# MCMainSch.net
KiCad netlist of a schematic drawn in Altium Designer
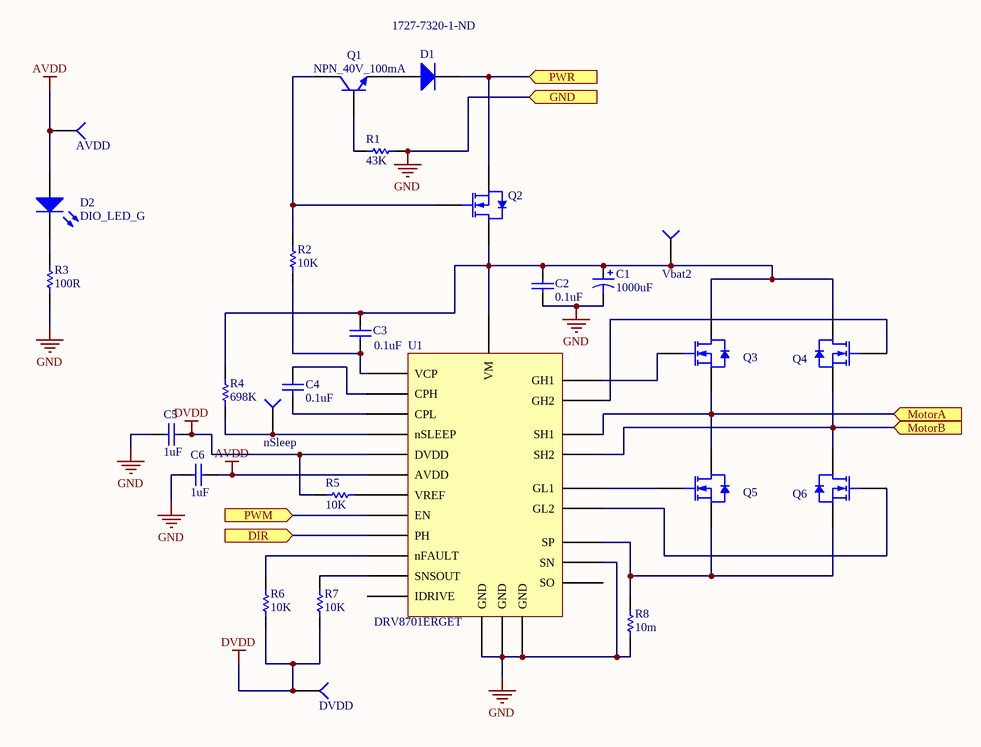
[diagram p0: MCMainSch.SchDoc]

(export (version "E")
  (design (tool "Eeschema 10.0.6"))
  (components
    (comp (ref "C1")
      (value "1000uF")
      (footprint "CAPR-2/4h6.8")
      (description "CAP ALUM 22UF 20% 50V RADIAL")
      (fields (field (name "MANUFACTURER") "Wurth Electronics Inc.") (field (name "MPN") "860020672011"))
      (libsource (lib "UWRT_Schematic_Library_2019") (part "CAP_22uF_POL"))
    )
    (comp (ref "C2")
      (value "0.1uF")
      (footprint "CAPC0603(1608)55_N")
      (description "CAP CER 0.1UF 16V X7R 0603")
      (fields (field (name "MPN") "CC0603KRX7R7BB104") (field (name "MANUFACTURER") "Yageo"))
      (libsource (lib "UWRT_Schematic_Library_2019") (part "CAP_0.1uF_16V_0603"))
    )
    (comp (ref "C3")
      (value "0.1uF")
      (footprint "CAPC0603(1608)55_N")
      (description "CAP CER 0.1UF 16V X7R 0603")
      (fields (field (name "MPN") "CC0603KRX7R7BB104") (field (name "MANUFACTURER") "Yageo"))
      (libsource (lib "UWRT_Schematic_Library_2019") (part "CAP_0.1uF_16V_0603"))
    )
    (comp (ref "C4")
      (value "0.1uF")
      (footprint "CAPC0603(1608)55_N")
      (description "CAP CER 0.1UF 16V X7R 0603")
      (fields (field (name "MPN") "CC0603KRX7R7BB104") (field (name "MANUFACTURER") "Yageo"))
      (libsource (lib "UWRT_Schematic_Library_2019") (part "CAP_0.1uF_16V_0603"))
    )
    (comp (ref "C5")
      (value "1uF")
      (footprint "CAPC0603(1608)55_N")
      (description "CAP CER 1UF 16V Y5V 0603")
      (fields (field (name "MPN") "CC0603ZRY5V7BB105") (field (name "MANUFACTURER") "Yageo"))
      (libsource (lib "UWRT_Schematic_Library_2019") (part "CAP_1uF_16V_0603"))
    )
    (comp (ref "C6")
      (value "1uF")
      (footprint "CAPC0603(1608)55_N")
      (description "CAP CER 1UF 16V Y5V 0603")
      (fields (field (name "MPN") "CC0603ZRY5V7BB105") (field (name "MANUFACTURER") "Yageo"))
      (libsource (lib "UWRT_Schematic_Library_2019") (part "CAP_1uF_16V_0603"))
    )
    (comp (ref "D1")
      (value "0")
      (footprint "DIODSOD-123")
      (description "ESD PROTECTION DIODE")
      (fields
        (field (name "MPN") "BAS16GW")
        (field (name "MANUFACTURER") "Nexperia")
        (field (name "SUPPLIER PART NUMBER 1") "1727-7320-1-ND")
      )
      (libsource (lib "UWRT_Schematic_Library_2019") (part "DIO_BAS16GW"))
    )
    (comp (ref "D2")
      (value "DIO_LED_G")
      (footprint "LED_0805_LINE")
      (description "LED GREEN DIFFUSED 0805 SMD")
      (fields (field (name "MPN") "LG R971-KN-1") (field (name "MANUFACTURER") "OSRAM"))
      (libsource (lib "UWRT_Schematic_Library_2019") (part "DIO_LED_G"))
    )
    (comp (ref "Q1")
      (value "NPN_40V_100mA")
      (footprint "SOT23-3")
      (description "TRANS NPN 40V 0.2A SOT23")
      (fields (field (name "MANUFACTURER") "Micro Commercial Co") (field (name "MPN") "MMBT3904-TP"))
      (libsource (lib "UWRT_Schematic_Library_2019") (part "NPN_40V_100mA"))
    )
    (comp (ref "Q2")
      (value "NMOS_40V_75A")
      (footprint "SOT404")
      (description "MOSFET N-CH 40V 75A D2PAK")
      (fields (field (name "MPN") "BUK768R1-40E,118") (field (name "MANUFACTURER") "Nexperia USA Inc."))
      (libsource (lib "UWRT_Schematic_Library_2019") (part "NMOS_40V_75A"))
    )
    (comp (ref "Q3")
      (value "NMOS_40V_75A")
      (footprint "SOT404")
      (description "MOSFET N-CH 40V 75A D2PAK")
      (fields (field (name "MPN") "BUK768R1-40E,118") (field (name "MANUFACTURER") "Nexperia USA Inc."))
      (libsource (lib "UWRT_Schematic_Library_2019") (part "NMOS_40V_75A"))
    )
    (comp (ref "Q4")
      (value "NMOS_40V_75A")
      (footprint "SOT404")
      (description "MOSFET N-CH 40V 75A D2PAK")
      (fields (field (name "MPN") "BUK768R1-40E,118") (field (name "MANUFACTURER") "Nexperia USA Inc."))
      (libsource (lib "UWRT_Schematic_Library_2019") (part "NMOS_40V_75A"))
    )
    (comp (ref "Q5")
      (value "NMOS_40V_75A")
      (footprint "SOT404")
      (description "MOSFET N-CH 40V 75A D2PAK")
      (fields (field (name "MPN") "BUK768R1-40E,118") (field (name "MANUFACTURER") "Nexperia USA Inc."))
      (libsource (lib "UWRT_Schematic_Library_2019") (part "NMOS_40V_75A"))
    )
    (comp (ref "Q6")
      (value "NMOS_40V_75A")
      (footprint "SOT404")
      (description "MOSFET N-CH 40V 75A D2PAK")
      (fields (field (name "MPN") "BUK768R1-40E,118") (field (name "MANUFACTURER") "Nexperia USA Inc."))
      (libsource (lib "UWRT_Schematic_Library_2019") (part "NMOS_40V_75A"))
    )
    (comp (ref "R1")
      (value "43K")
      (footprint "RESC0603(1608)_N")
      (description "RES SMD 43K OHM 5% 1/10W 0603")
      (fields (field (name "MANUFACTURER") "Yageo") (field (name "MPN") "RC0603JR-0743KL"))
      (libsource (lib "UWRT_Schematic_Library_2019") (part "RES_43K_0603"))
    )
    (comp (ref "R2")
      (value "10K")
      (footprint "RESC0603(1608)_N")
      (description "RES SMD 10K OHM 5% 1/10W 0603")
      (fields (field (name "MANUFACTURER") "Yageo") (field (name "MPN") "RC0603JR-0710KL"))
      (libsource (lib "UWRT_Schematic_Library_2019") (part "RES_10K_0603"))
    )
    (comp (ref "R3")
      (value "100R")
      (footprint "RESC0603(1608)_N")
      (description "RES SMD 0 OHM JUMPER 1/10W 0603")
      (fields (field (name "MANUFACTURER") "Yageo") (field (name "MPN") "RC0603JR-070RL"))
      (libsource (lib "UWRT_Schematic_Library_2019") (part "RES_0R_0603"))
    )
    (comp (ref "R4")
      (value "698K")
      (footprint "RESC0603(1608)_N")
      (description "RES SMD 698K OHM 1% 1/10W 0603")
      (fields (field (name "MANUFACTURER") "Yageo") (field (name "MPN") "RC0603FR-07698KL"))
      (libsource (lib "UWRT_Schematic_Library_2019") (part "RES_698K_0603"))
    )
    (comp (ref "R5")
      (value "10K")
      (footprint "RESC0603(1608)_N")
      (description "RES SMD 10K OHM 5% 1/10W 0603")
      (fields (field (name "MANUFACTURER") "Yageo") (field (name "MPN") "RC0603JR-0710KL"))
      (libsource (lib "UWRT_Schematic_Library_2019") (part "RES_10K_0603"))
    )
    (comp (ref "R6")
      (value "10K")
      (footprint "RESC0603(1608)_N")
      (description "RES SMD 10K OHM 5% 1/10W 0603")
      (fields (field (name "MANUFACTURER") "Yageo") (field (name "MPN") "RC0603JR-0710KL"))
      (libsource (lib "UWRT_Schematic_Library_2019") (part "RES_10K_0603"))
    )
    (comp (ref "R7")
      (value "10K")
      (footprint "RESC0603(1608)_N")
      (description "RES SMD 10K OHM 5% 1/10W 0603")
      (fields (field (name "MANUFACTURER") "Yageo") (field (name "MPN") "RC0603JR-0710KL"))
      (libsource (lib "UWRT_Schematic_Library_2019") (part "RES_10K_0603"))
    )
    (comp (ref "R8")
      (value "10m")
      (footprint "STAC-CSS2725-099H_V")
      (description "RES SMD 10mOHM 1% 4W 2728")
      (fields (field (name "MANUFACTURER") "Yageo") (field (name "MPN") "RC0603FR-07698KL"))
      (libsource (lib "UWRT_Schematic_Library_2019") (part "RES_10m_2728"))
    )
    (comp (ref "TP1")
      (value "AVDD")
      (footprint "TESTPOINT")
      (description "TESTPOINT_SMD")
      (libsource (lib "UWRT_Schematic_Library_2019") (part "*"))
    )
    (comp (ref "TP2")
      (value "Vbat2")
      (footprint "TESTPOINT")
      (description "TESTPOINT_SMD")
      (libsource (lib "UWRT_Schematic_Library_2019") (part "*"))
    )
    (comp (ref "TP3")
      (value "nSleep")
      (footprint "TESTPOINT")
      (description "TESTPOINT_SMD")
      (libsource (lib "UWRT_Schematic_Library_2019") (part "*"))
    )
    (comp (ref "TP4")
      (value "DVDD")
      (footprint "TESTPOINT")
      (description "TESTPOINT_SMD")
      (libsource (lib "UWRT_Schematic_Library_2019") (part "*"))
    )
    (comp (ref "U1")
      (value "DRV8701ERGET")
      (footprint "VFQFPN-24_N")
      (fields (field (name "MANUFACTURER") "Texas Instruments"))
      (libsource (lib "UWRT_Schematic_Library_2019") (part "IC Motor Driver"))
    )
  )
  (nets
    (net (code "1") (name "/DIR") (class "Default")
      (node (ref "U1") (pin "15") (pinfunction "PH_15") (pintype "passive"))
    )
    (net (code "2") (name "/MotorA") (class "Default")
      (node (ref "Q3") (pin "3") (pinfunction "S_3") (pintype "passive"))
      (node (ref "Q5") (pin "4") (pinfunction "D_4") (pintype "passive"))
      (node (ref "U1") (pin "18") (pinfunction "SH1_18") (pintype "passive"))
    )
    (net (code "3") (name "/MotorB") (class "Default")
      (node (ref "Q4") (pin "3") (pinfunction "S_3") (pintype "passive"))
      (node (ref "Q6") (pin "4") (pinfunction "D_4") (pintype "passive"))
      (node (ref "U1") (pin "23") (pinfunction "SH2_23") (pintype "passive"))
    )
    (net (code "4") (name "/PWM") (class "Default")
      (node (ref "U1") (pin "14") (pinfunction "EN_14") (pintype "passive"))
    )
    (net (code "5") (name "/PWR") (class "Default")
      (node (ref "D1") (pin "2") (pinfunction "K_2") (pintype "passive"))
      (node (ref "Q2") (pin "3") (pinfunction "S_3") (pintype "passive"))
    )
    (net (code "6") (name "AVDD") (class "Default")
      (node (ref "C6") (pin "2") (pinfunction "2_2") (pintype "passive"))
      (node (ref "D2") (pin "1") (pinfunction "A_1") (pintype "passive"))
      (node (ref "TP1") (pin "1") (pinfunction "=value_1") (pintype "passive"))
      (node (ref "U1") (pin "7") (pinfunction "AVDD_7") (pintype "passive"))
    )
    (net (code "7") (name "DVDD") (class "Default")
      (node (ref "C5") (pin "2") (pinfunction "2_2") (pintype "passive"))
      (node (ref "R5") (pin "1") (pinfunction "1_1") (pintype "passive"))
      (node (ref "R6") (pin "1") (pinfunction "1_1") (pintype "passive"))
      (node (ref "R7") (pin "1") (pinfunction "1_1") (pintype "passive"))
      (node (ref "TP4") (pin "1") (pinfunction "=value_1") (pintype "passive"))
      (node (ref "U1") (pin "8") (pinfunction "DVDD_8") (pintype "passive"))
    )
    (net (code "8") (name "GND") (class "Default")
      (node (ref "C1") (pin "2") (pinfunction "2_2") (pintype "passive"))
      (node (ref "C2") (pin "1") (pinfunction "1_1") (pintype "passive"))
      (node (ref "C5") (pin "1") (pinfunction "1_1") (pintype "passive"))
      (node (ref "C6") (pin "1") (pinfunction "1_1") (pintype "passive"))
      (node (ref "R1") (pin "1") (pinfunction "1_1") (pintype "passive"))
      (node (ref "R3") (pin "1") (pinfunction "1_1") (pintype "passive"))
      (node (ref "R8") (pin "1") (pinfunction "1_1") (pintype "passive"))
      (node (ref "U1") (pin "16") (pinfunction "GND_16") (pintype "passive"))
      (node (ref "U1") (pin "20") (pinfunction "SN_20") (pintype "passive"))
      (node (ref "U1") (pin "25") (pinfunction "GND_25") (pintype "passive"))
      (node (ref "U1") (pin "5") (pinfunction "GND_5") (pintype "passive"))
    )
    (net (code "9") (name "Net-(D1-A)") (class "Default")
      (node (ref "D1") (pin "1") (pinfunction "A_1") (pintype "passive"))
      (node (ref "Q1") (pin "2") (pinfunction "E_2") (pintype "passive"))
    )
    (net (code "10") (name "Net-(D2-K)") (class "Default")
      (node (ref "D2") (pin "2") (pinfunction "K_2") (pintype "passive"))
      (node (ref "R3") (pin "2") (pinfunction "2_2") (pintype "passive"))
    )
    (net (code "11") (name "Net-(Q1-B)") (class "Default")
      (node (ref "Q1") (pin "1") (pinfunction "B_1") (pintype "passive"))
      (node (ref "R1") (pin "2") (pinfunction "2_2") (pintype "passive"))
    )
    (net (code "12") (name "Net-(Q1-C)") (class "Default")
      (node (ref "Q1") (pin "3") (pinfunction "C_3") (pintype "passive"))
      (node (ref "Q2") (pin "1") (pinfunction "G_1") (pintype "passive"))
      (node (ref "R2") (pin "2") (pinfunction "2_2") (pintype "passive"))
    )
    (net (code "13") (name "Net-(Q2-D)") (class "Default")
      (node (ref "C1") (pin "1") (pinfunction "1_1") (pintype "passive"))
      (node (ref "C2") (pin "2") (pinfunction "2_2") (pintype "passive"))
      (node (ref "C3") (pin "2") (pinfunction "2_2") (pintype "passive"))
      (node (ref "Q2") (pin "4") (pinfunction "D_4") (pintype "passive"))
      (node (ref "Q3") (pin "4") (pinfunction "D_4") (pintype "passive"))
      (node (ref "Q4") (pin "4") (pinfunction "D_4") (pintype "passive"))
      (node (ref "R4") (pin "2") (pinfunction "2_2") (pintype "passive"))
      (node (ref "TP2") (pin "1") (pinfunction "=value_1") (pintype "passive"))
      (node (ref "U1") (pin "1") (pinfunction "VM_1") (pintype "passive"))
    )
    (net (code "14") (name "Net-(Q3-G)") (class "Default")
      (node (ref "Q3") (pin "1") (pinfunction "G_1") (pintype "passive"))
      (node (ref "U1") (pin "17") (pinfunction "GH1_17") (pintype "passive"))
    )
    (net (code "15") (name "Net-(Q4-G)") (class "Default")
      (node (ref "Q4") (pin "1") (pinfunction "G_1") (pintype "passive"))
      (node (ref "U1") (pin "24") (pinfunction "GH2_24") (pintype "passive"))
    )
    (net (code "16") (name "Net-(Q5-G)") (class "Default")
      (node (ref "Q5") (pin "1") (pinfunction "G_1") (pintype "passive"))
      (node (ref "U1") (pin "19") (pinfunction "GL1_19") (pintype "passive"))
    )
    (net (code "17") (name "Net-(Q5-S)") (class "Default")
      (node (ref "Q5") (pin "3") (pinfunction "S_3") (pintype "passive"))
      (node (ref "Q6") (pin "3") (pinfunction "S_3") (pintype "passive"))
      (node (ref "R8") (pin "2") (pinfunction "2_2") (pintype "passive"))
      (node (ref "U1") (pin "21") (pinfunction "SP_21") (pintype "passive"))
    )
    (net (code "18") (name "Net-(Q6-G)") (class "Default")
      (node (ref "Q6") (pin "1") (pinfunction "G_1") (pintype "passive"))
      (node (ref "U1") (pin "22") (pinfunction "GL2_22") (pintype "passive"))
    )
    (net (code "19") (name "Net-(TP3-=value)") (class "Default")
      (node (ref "R4") (pin "1") (pinfunction "1_1") (pintype "passive"))
      (node (ref "TP3") (pin "1") (pinfunction "=value_1") (pintype "passive"))
      (node (ref "U1") (pin "13") (pinfunction "nSLEEP_13") (pintype "passive"))
    )
    (net (code "20") (name "Net-(U1-CPH)") (class "Default")
      (node (ref "C4") (pin "2") (pinfunction "2_2") (pintype "passive"))
      (node (ref "U1") (pin "3") (pinfunction "CPH_3") (pintype "passive"))
    )
    (net (code "21") (name "Net-(U1-CPL)") (class "Default")
      (node (ref "C4") (pin "1") (pinfunction "1_1") (pintype "passive"))
      (node (ref "U1") (pin "4") (pinfunction "CPL_4") (pintype "passive"))
    )
    (net (code "22") (name "Net-(U1-SNSOUT)") (class "Default")
      (node (ref "R7") (pin "2") (pinfunction "2_2") (pintype "passive"))
      (node (ref "U1") (pin "10") (pinfunction "SNSOUT_10") (pintype "passive"))
    )
    (net (code "23") (name "Net-(U1-VCP)") (class "Default")
      (node (ref "C3") (pin "1") (pinfunction "1_1") (pintype "passive"))
      (node (ref "R2") (pin "1") (pinfunction "1_1") (pintype "passive"))
      (node (ref "U1") (pin "2") (pinfunction "VCP_2") (pintype "passive"))
    )
    (net (code "24") (name "Net-(U1-VREF)") (class "Default")
      (node (ref "R5") (pin "2") (pinfunction "2_2") (pintype "passive"))
      (node (ref "U1") (pin "6") (pinfunction "VREF_6") (pintype "passive"))
    )
    (net (code "25") (name "Net-(U1-nFAULT)") (class "Default")
      (node (ref "R6") (pin "2") (pinfunction "2_2") (pintype "passive"))
      (node (ref "U1") (pin "9") (pinfunction "nFAULT_9") (pintype "passive"))
    )
    (net (code "26") (name "unconnected-(U1-IDRIVE-Pad12)") (class "Default")
      (node (ref "U1") (pin "12") (pinfunction "IDRIVE_12") (pintype "passive"))
    )
    (net (code "27") (name "unconnected-(U1-SO-Pad11)") (class "Default")
      (node (ref "U1") (pin "11") (pinfunction "SO_11") (pintype "passive"))
    )
  )
)
